# qo-100-pa-tec-controller.net
KiCad netlist of a schematic drawn in EAGLE
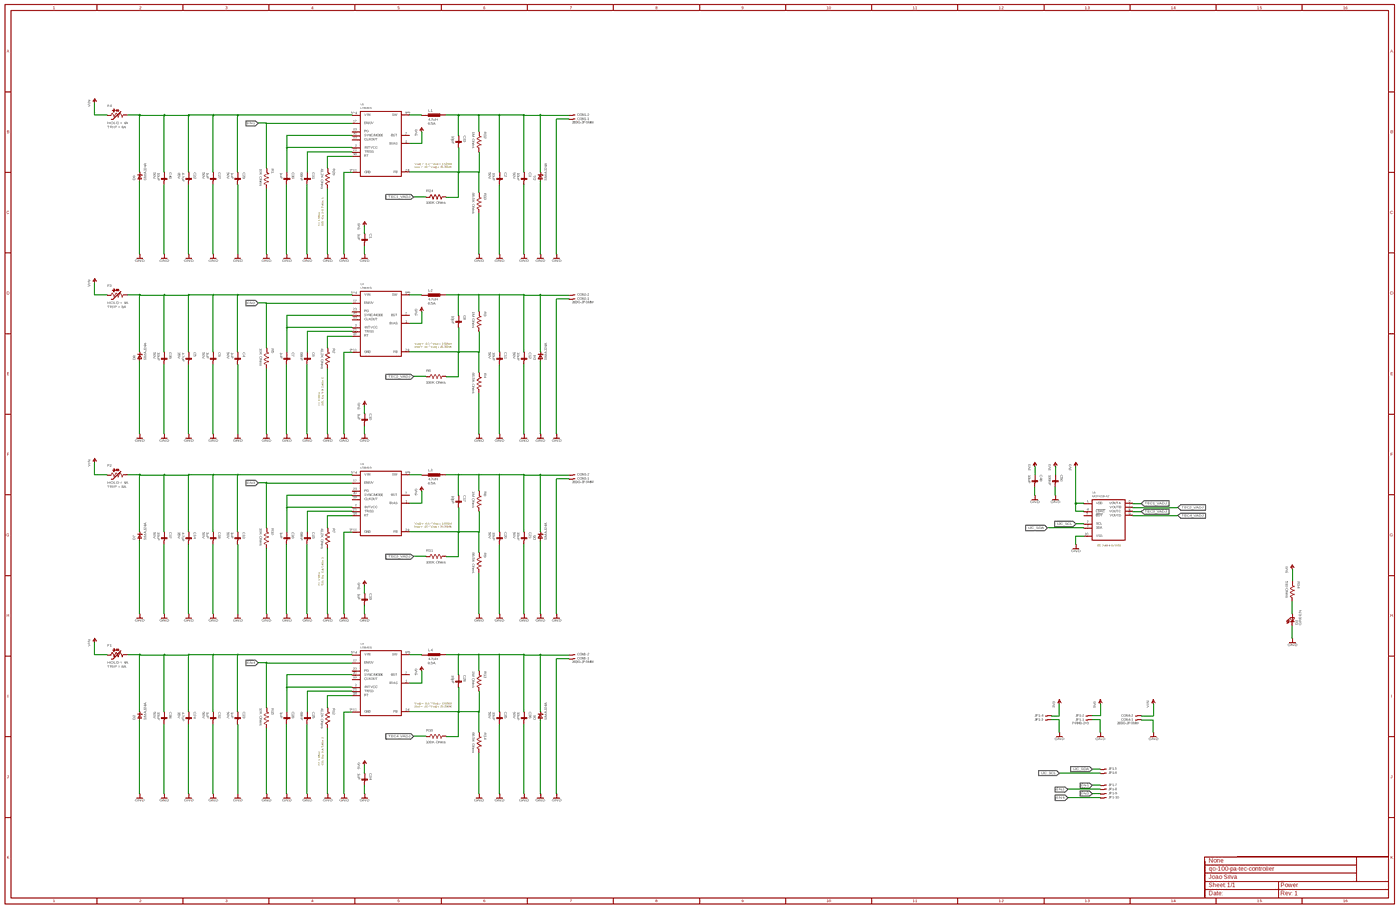
[diagram p0: schematic, sheet 1, overview]
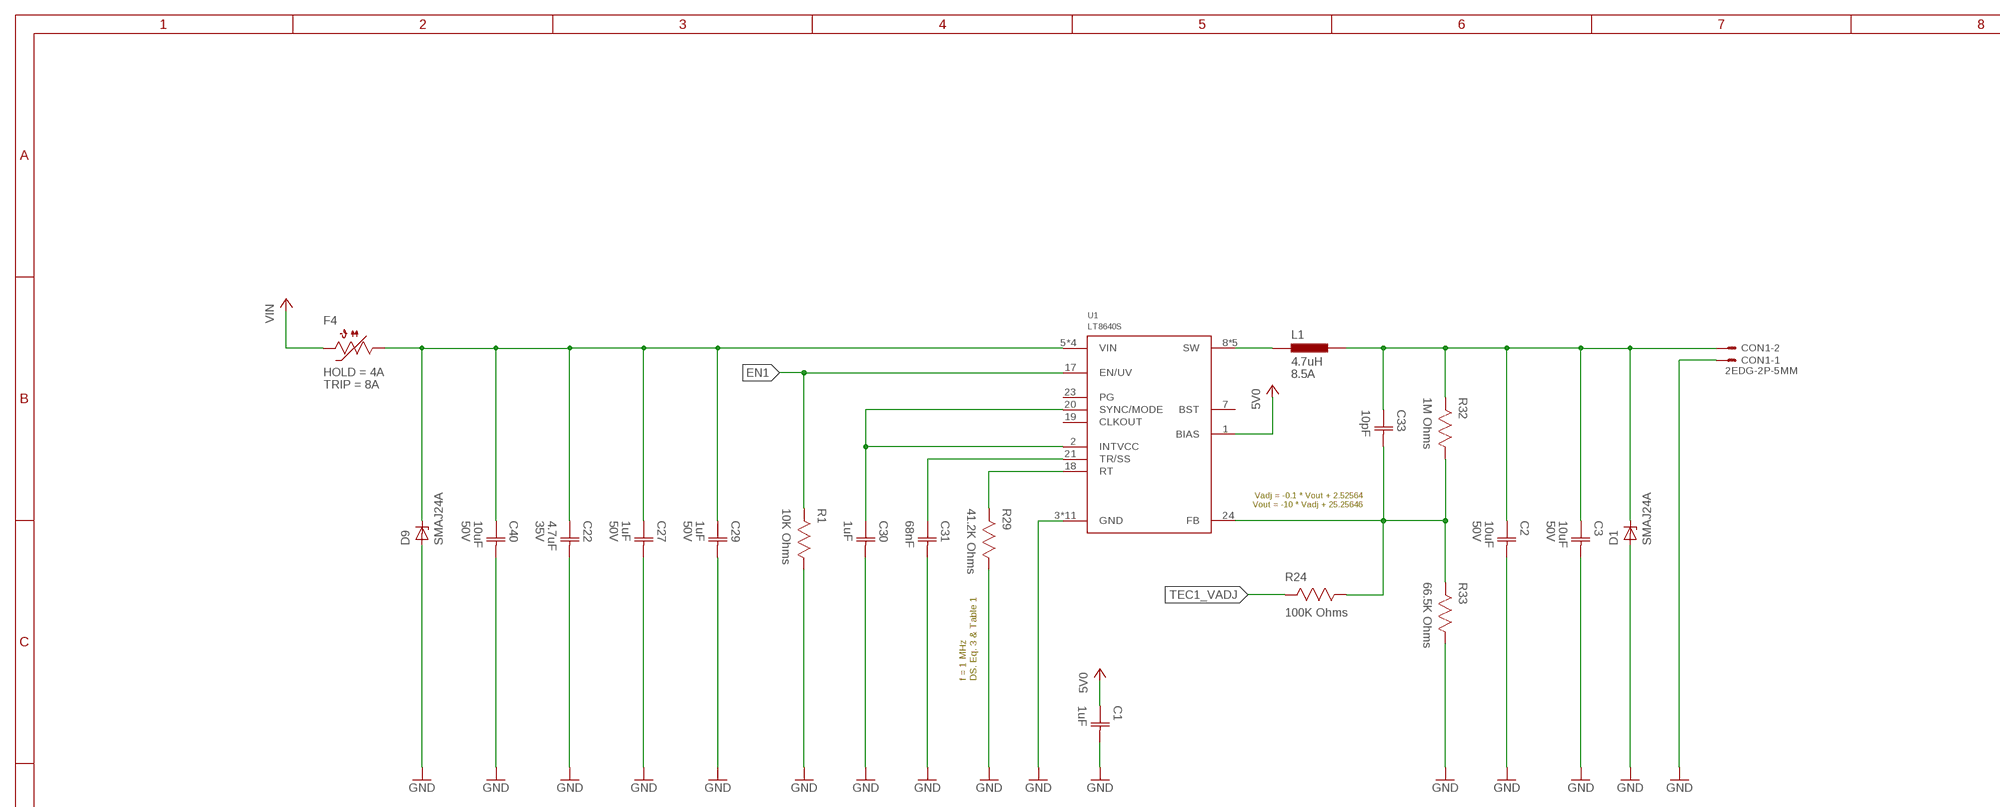
[diagram p1: schematic, sheet 1, part 1 of 4]
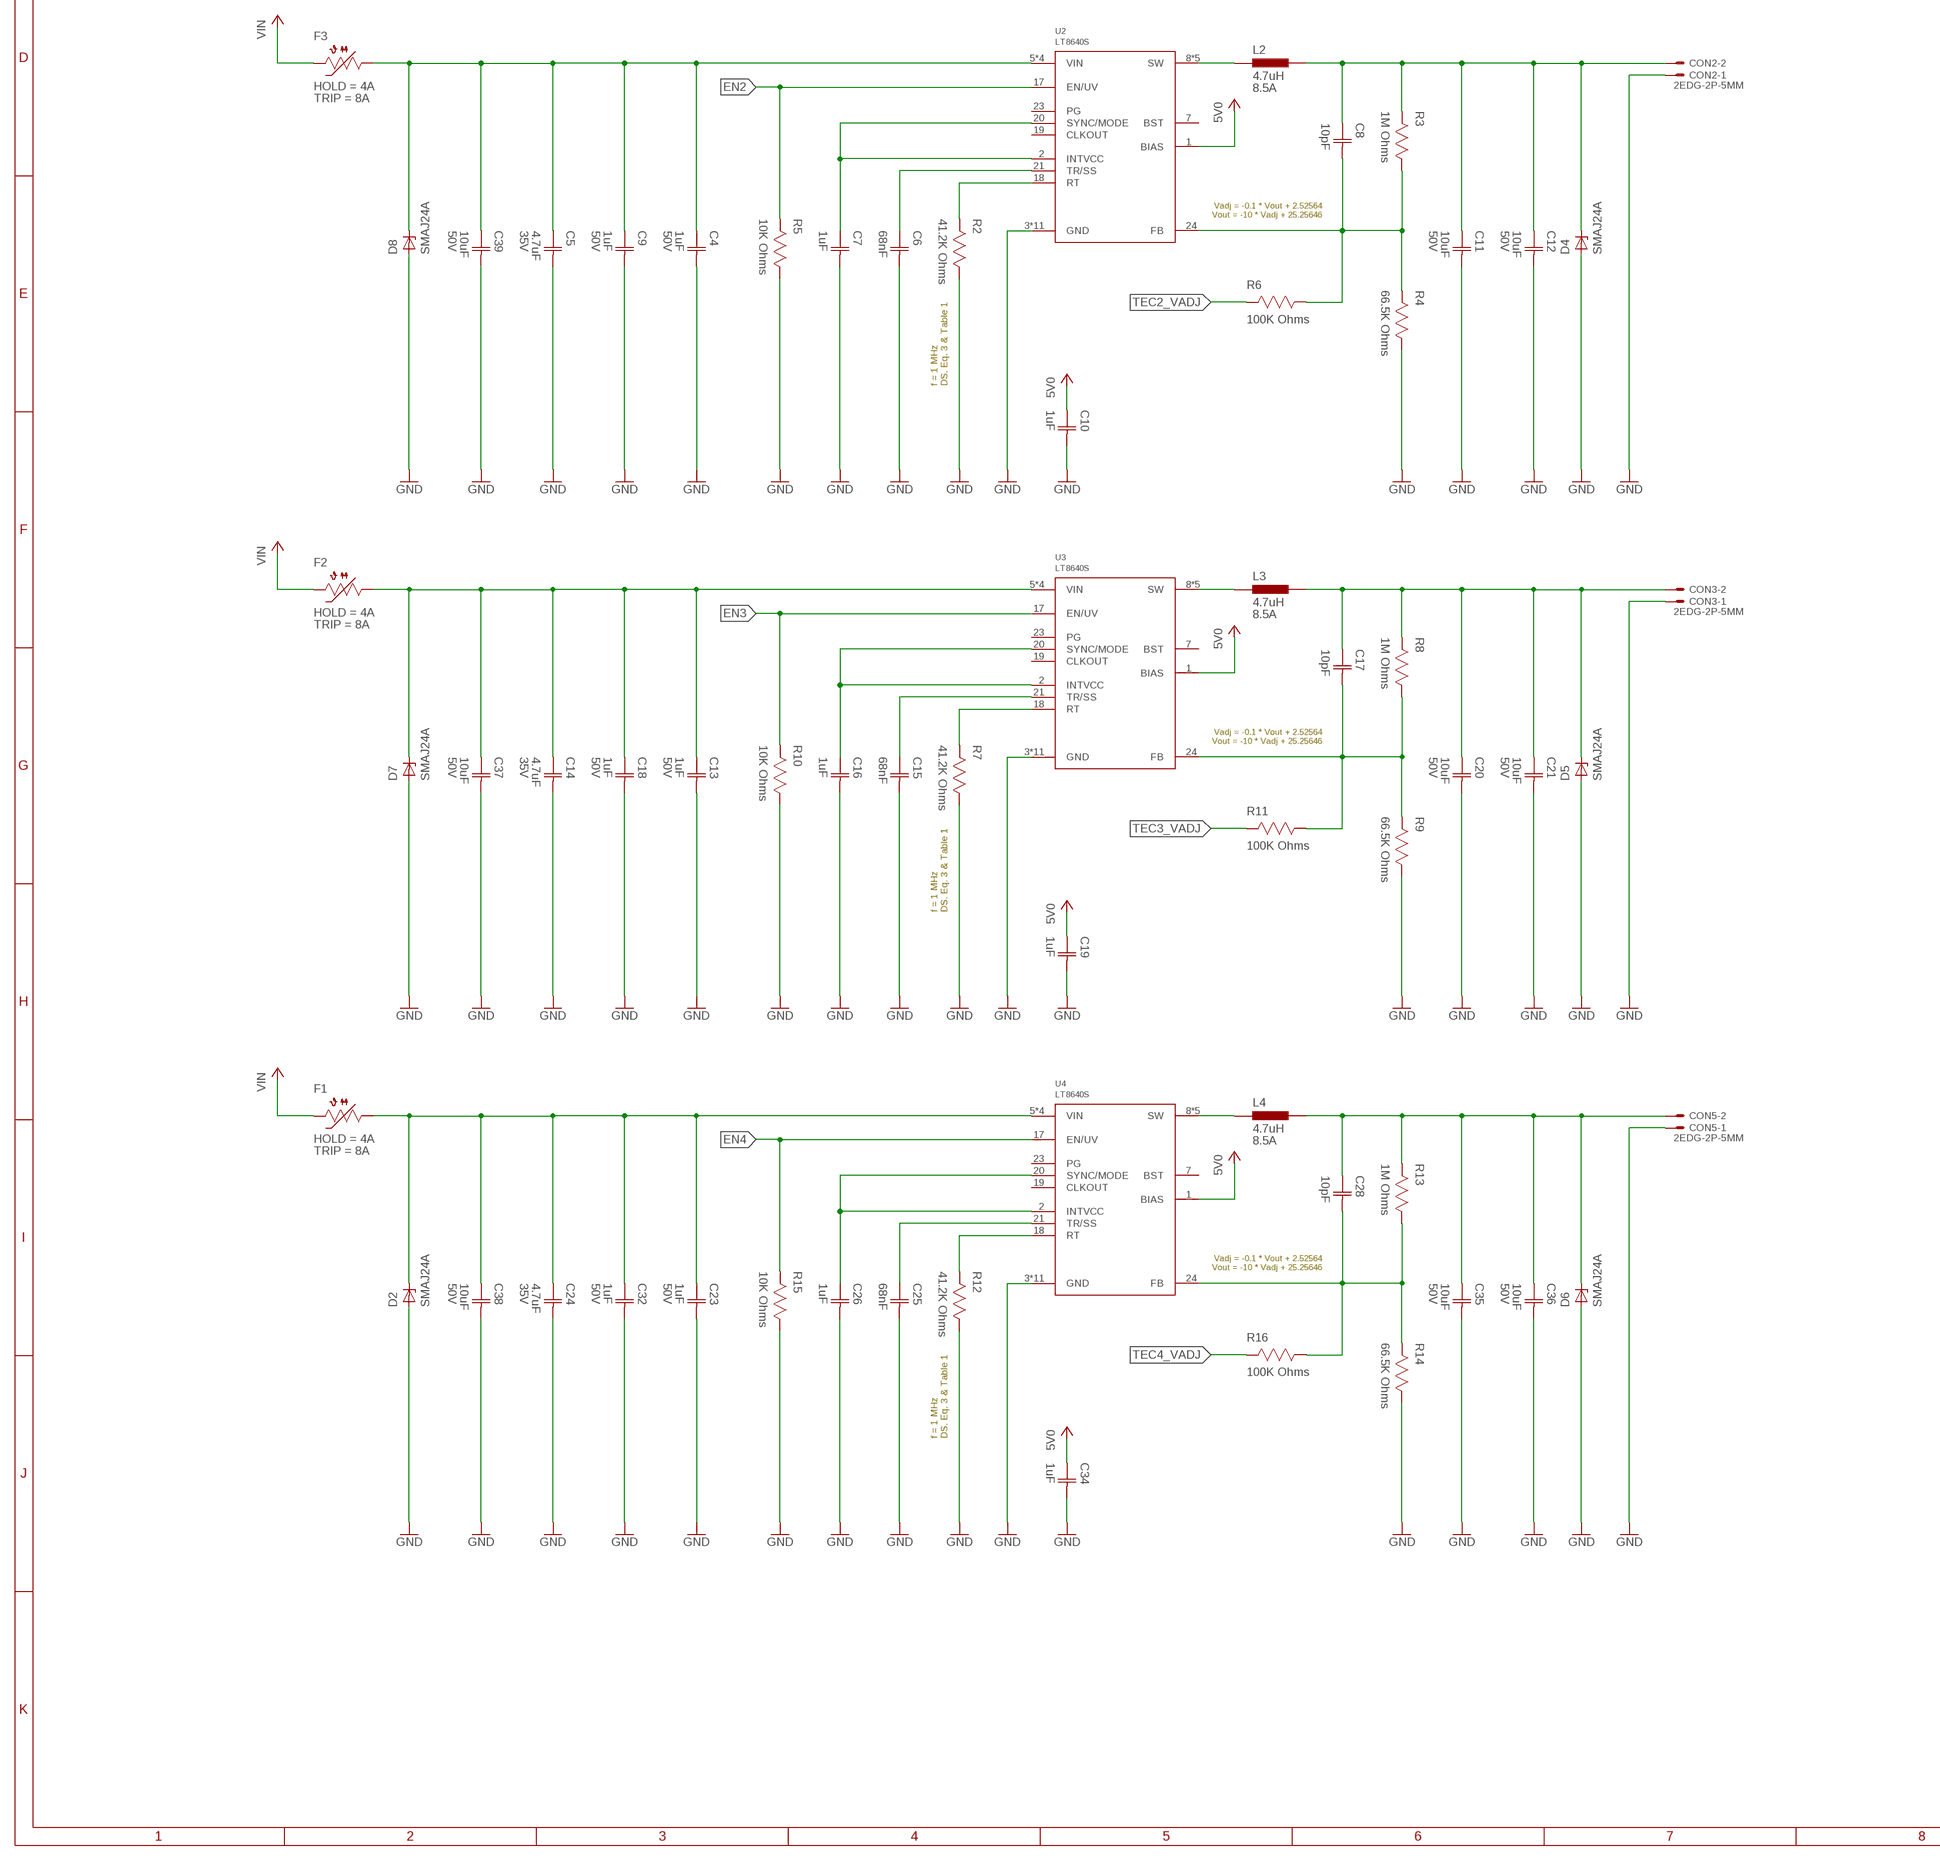
[diagram p2: schematic, sheet 1, part 2 of 4]
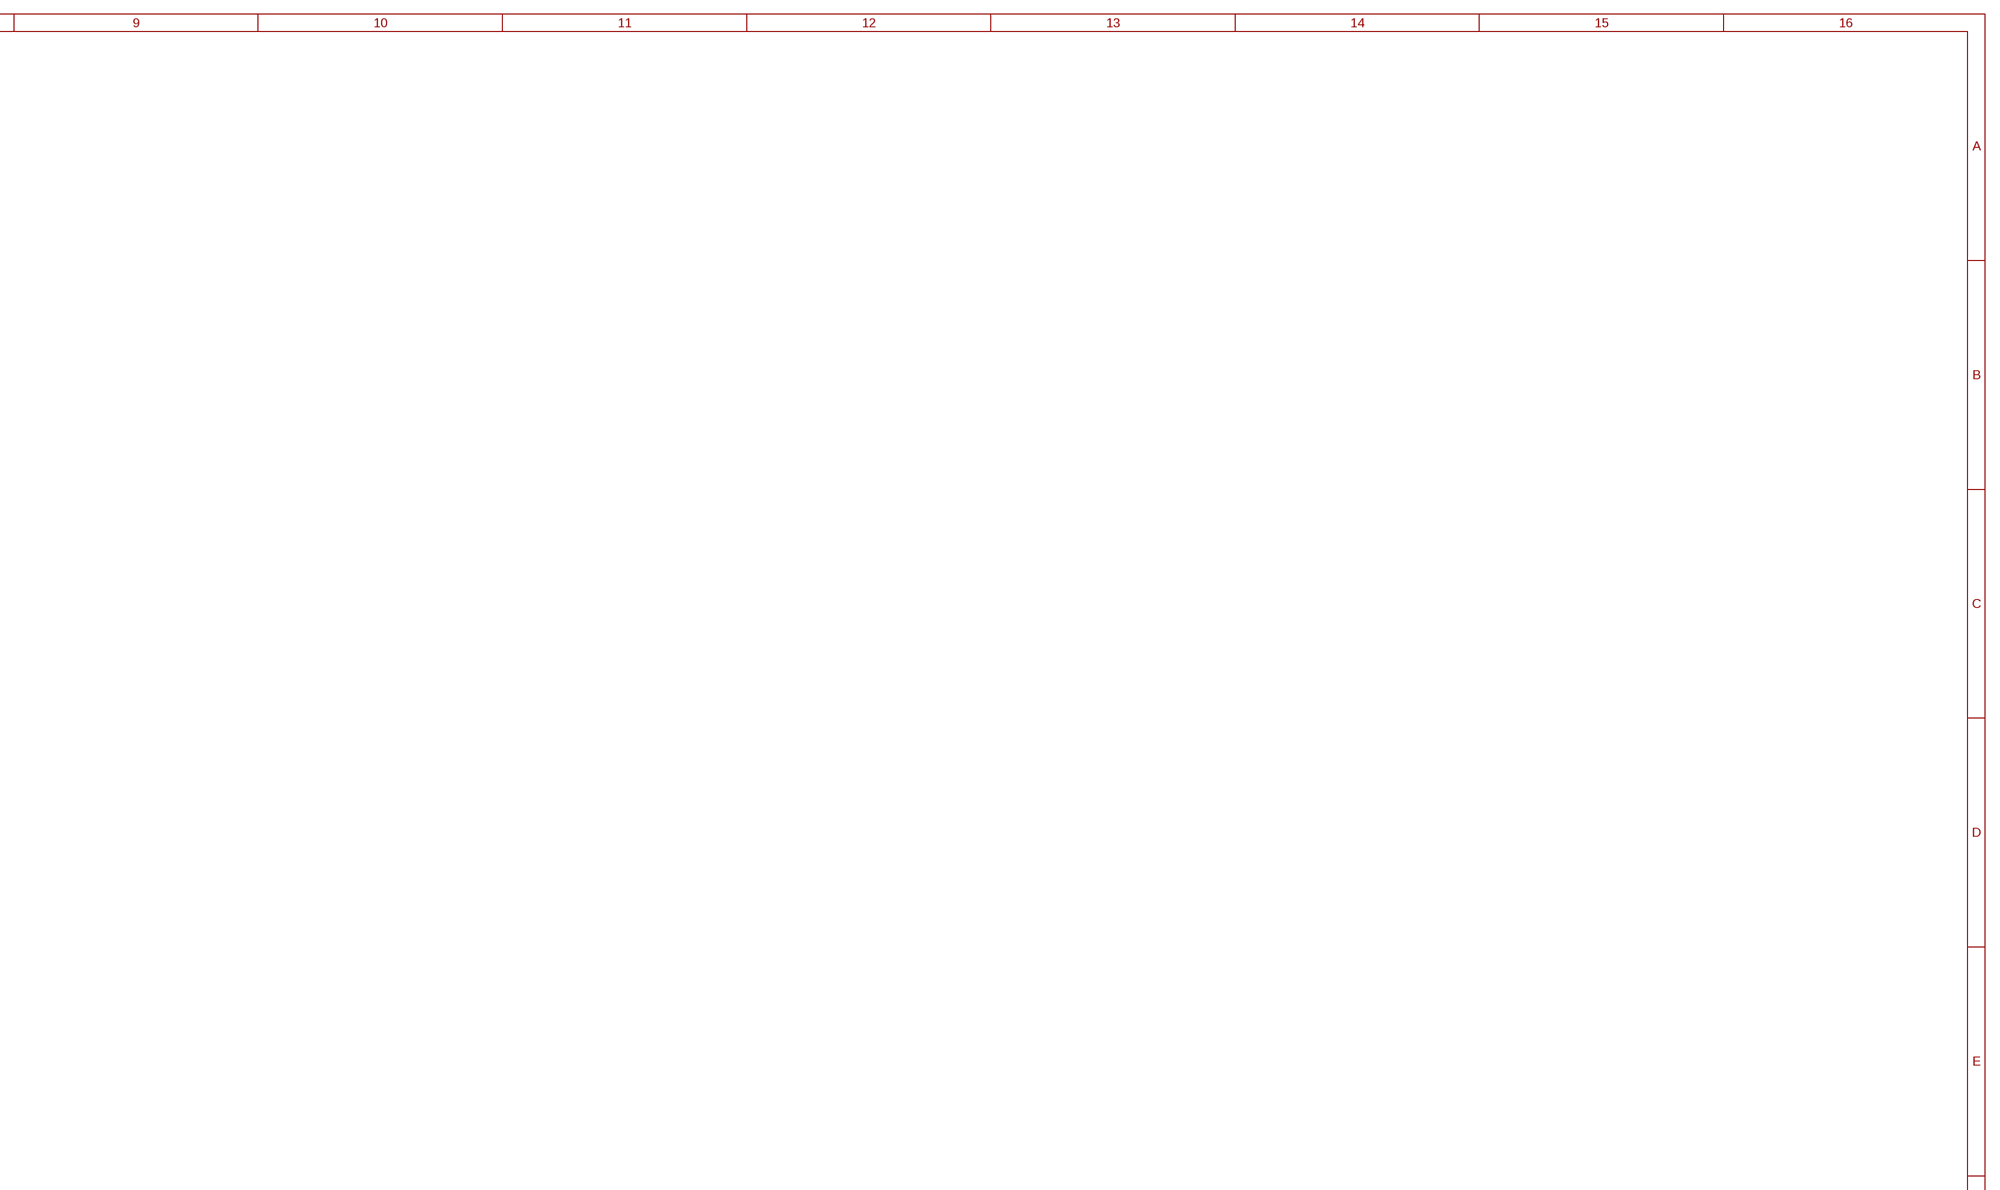
[diagram p3: schematic, sheet 1, part 3 of 4]
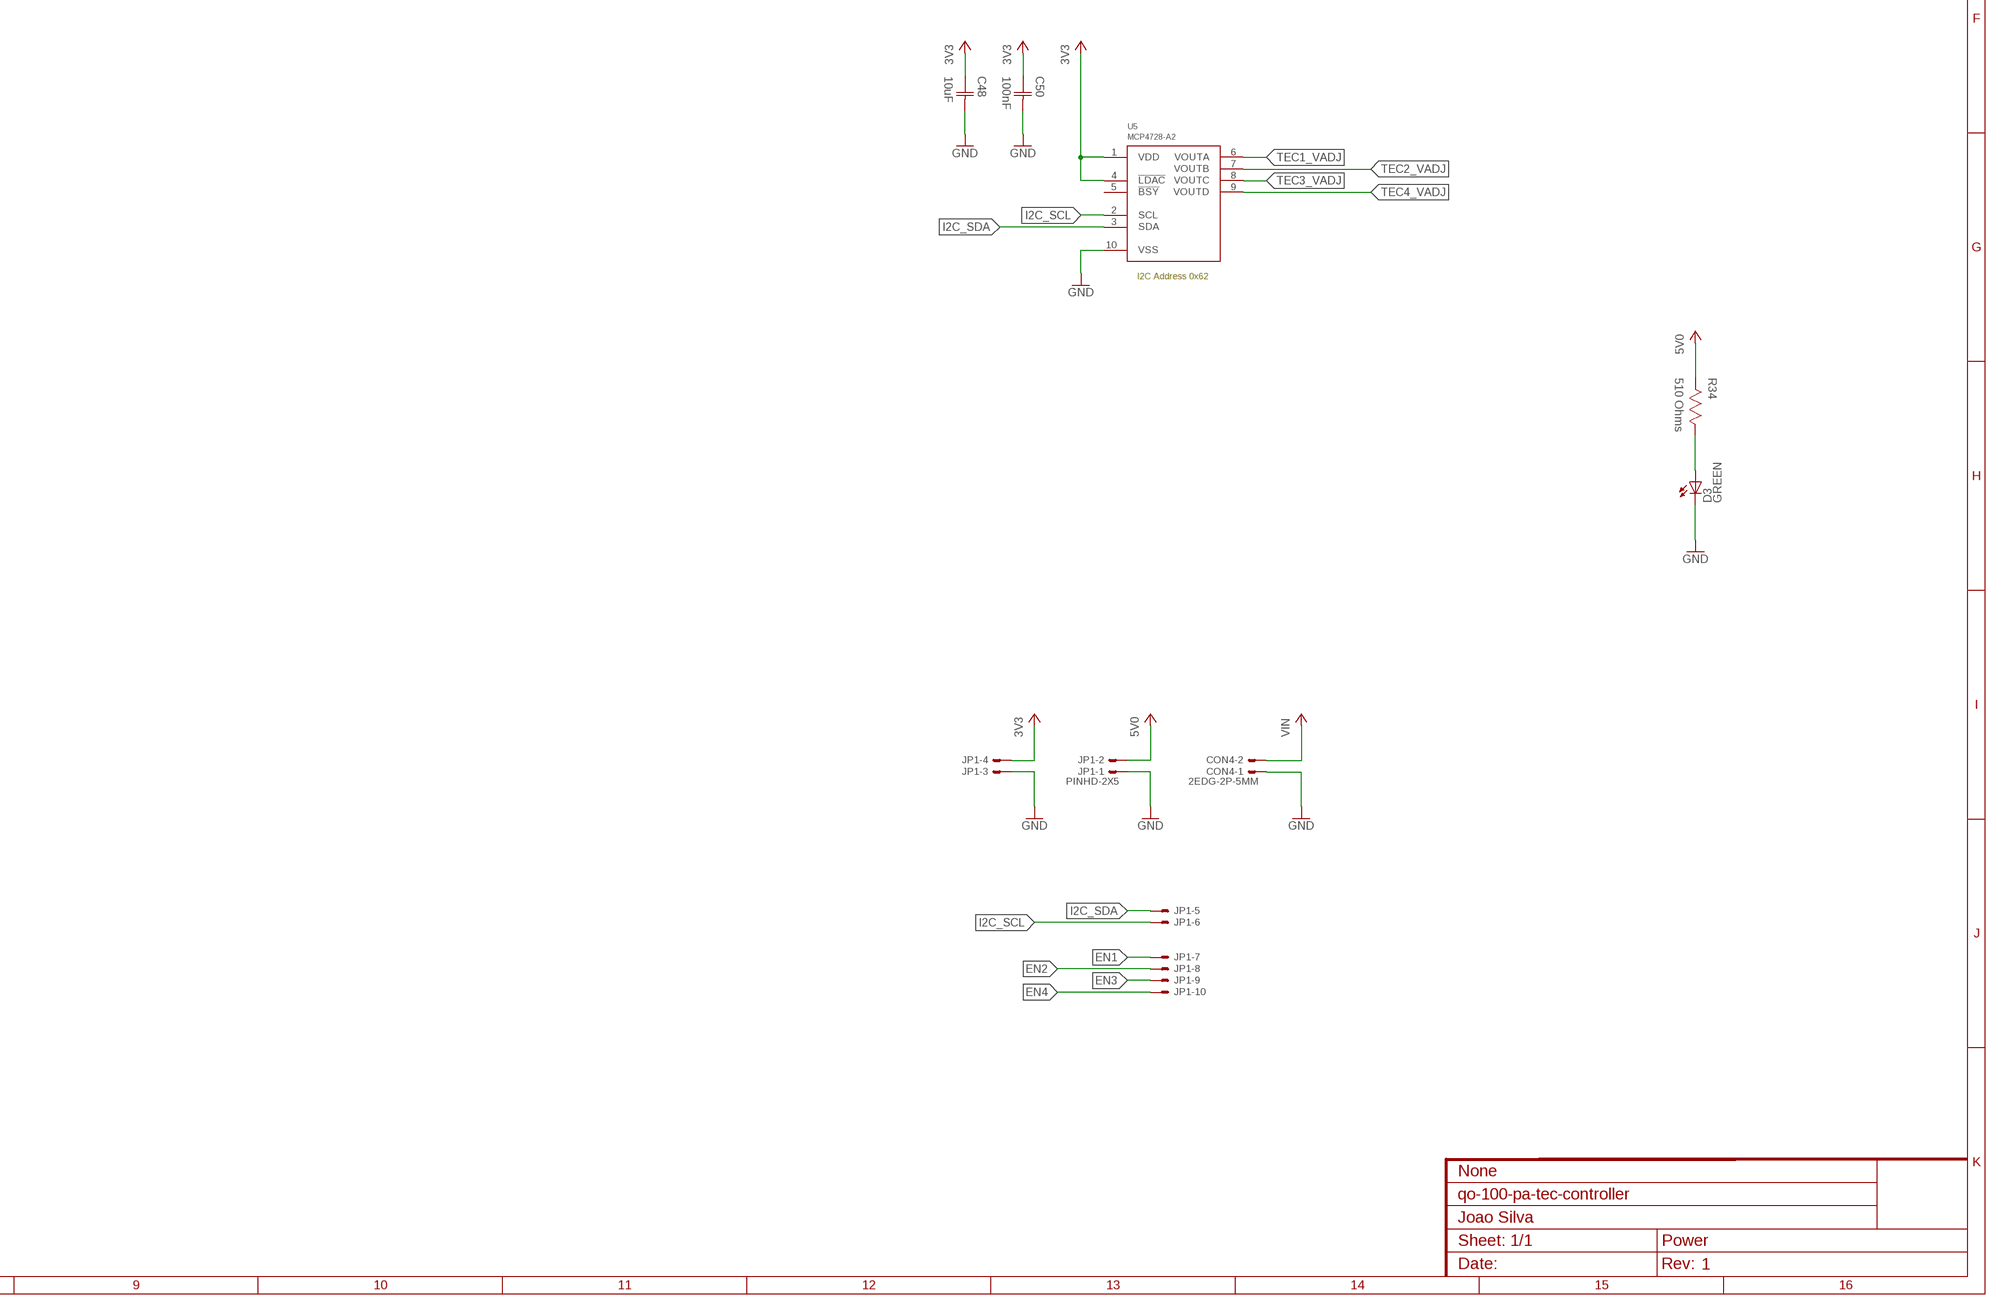
[diagram p4: schematic, sheet 1, part 4 of 4]

(export (version "E")
  (design (tool "Eeschema 10.0.6"))
  (components
    (comp (ref "C1")
      (value "1uF")
      (footprint "eagle-import:CAP0603")
      (libsource (lib "eagle-import") (part "CAPACITOR-0603"))
    )
    (comp (ref "C2")
      (value "10uF")
      (footprint "eagle-import:CAP1206")
      (fields (field (name "VOLTAGE") "50V"))
      (libsource (lib "eagle-import") (part "CAPACITOR-1206"))
    )
    (comp (ref "C3")
      (value "10uF")
      (footprint "eagle-import:CAP1206")
      (fields (field (name "VOLTAGE") "50V"))
      (libsource (lib "eagle-import") (part "CAPACITOR-1206"))
    )
    (comp (ref "C4")
      (value "1uF")
      (footprint "eagle-import:CAP0603")
      (fields (field (name "VOLTAGE") "50V"))
      (libsource (lib "eagle-import") (part "CAPACITOR-0603"))
    )
    (comp (ref "C5")
      (value "4.7uF")
      (footprint "eagle-import:CAP0603")
      (fields (field (name "VOLTAGE") "35V"))
      (libsource (lib "eagle-import") (part "CAPACITOR-0603"))
    )
    (comp (ref "C6")
      (value "68nF")
      (footprint "eagle-import:CAP0603")
      (libsource (lib "eagle-import") (part "CAPACITOR-0603"))
    )
    (comp (ref "C7")
      (value "1uF")
      (footprint "eagle-import:CAP0603")
      (libsource (lib "eagle-import") (part "CAPACITOR-0603"))
    )
    (comp (ref "C8")
      (value "10pF")
      (footprint "eagle-import:CAP0603")
      (libsource (lib "eagle-import") (part "CAPACITOR-0603"))
    )
    (comp (ref "C9")
      (value "1uF")
      (footprint "eagle-import:CAP0603")
      (fields (field (name "VOLTAGE") "50V"))
      (libsource (lib "eagle-import") (part "CAPACITOR-0603"))
    )
    (comp (ref "C10")
      (value "1uF")
      (footprint "eagle-import:CAP0603")
      (libsource (lib "eagle-import") (part "CAPACITOR-0603"))
    )
    (comp (ref "C11")
      (value "10uF")
      (footprint "eagle-import:CAP1206")
      (fields (field (name "VOLTAGE") "50V"))
      (libsource (lib "eagle-import") (part "CAPACITOR-1206"))
    )
    (comp (ref "C12")
      (value "10uF")
      (footprint "eagle-import:CAP1206")
      (fields (field (name "VOLTAGE") "50V"))
      (libsource (lib "eagle-import") (part "CAPACITOR-1206"))
    )
    (comp (ref "C13")
      (value "1uF")
      (footprint "eagle-import:CAP0603")
      (fields (field (name "VOLTAGE") "50V"))
      (libsource (lib "eagle-import") (part "CAPACITOR-0603"))
    )
    (comp (ref "C14")
      (value "4.7uF")
      (footprint "eagle-import:CAP0603")
      (fields (field (name "VOLTAGE") "35V"))
      (libsource (lib "eagle-import") (part "CAPACITOR-0603"))
    )
    (comp (ref "C15")
      (value "68nF")
      (footprint "eagle-import:CAP0603")
      (libsource (lib "eagle-import") (part "CAPACITOR-0603"))
    )
    (comp (ref "C16")
      (value "1uF")
      (footprint "eagle-import:CAP0603")
      (libsource (lib "eagle-import") (part "CAPACITOR-0603"))
    )
    (comp (ref "C17")
      (value "10pF")
      (footprint "eagle-import:CAP0603")
      (libsource (lib "eagle-import") (part "CAPACITOR-0603"))
    )
    (comp (ref "C18")
      (value "1uF")
      (footprint "eagle-import:CAP0603")
      (fields (field (name "VOLTAGE") "50V"))
      (libsource (lib "eagle-import") (part "CAPACITOR-0603"))
    )
    (comp (ref "C19")
      (value "1uF")
      (footprint "eagle-import:CAP0603")
      (libsource (lib "eagle-import") (part "CAPACITOR-0603"))
    )
    (comp (ref "C20")
      (value "10uF")
      (footprint "eagle-import:CAP1206")
      (fields (field (name "VOLTAGE") "50V"))
      (libsource (lib "eagle-import") (part "CAPACITOR-1206"))
    )
    (comp (ref "C21")
      (value "10uF")
      (footprint "eagle-import:CAP1206")
      (fields (field (name "VOLTAGE") "50V"))
      (libsource (lib "eagle-import") (part "CAPACITOR-1206"))
    )
    (comp (ref "C22")
      (value "4.7uF")
      (footprint "eagle-import:CAP0603")
      (fields (field (name "VOLTAGE") "35V"))
      (libsource (lib "eagle-import") (part "CAPACITOR-0603"))
    )
    (comp (ref "C23")
      (value "1uF")
      (footprint "eagle-import:CAP0603")
      (fields (field (name "VOLTAGE") "50V"))
      (libsource (lib "eagle-import") (part "CAPACITOR-0603"))
    )
    (comp (ref "C24")
      (value "4.7uF")
      (footprint "eagle-import:CAP0603")
      (fields (field (name "VOLTAGE") "35V"))
      (libsource (lib "eagle-import") (part "CAPACITOR-0603"))
    )
    (comp (ref "C25")
      (value "68nF")
      (footprint "eagle-import:CAP0603")
      (libsource (lib "eagle-import") (part "CAPACITOR-0603"))
    )
    (comp (ref "C26")
      (value "1uF")
      (footprint "eagle-import:CAP0603")
      (libsource (lib "eagle-import") (part "CAPACITOR-0603"))
    )
    (comp (ref "C27")
      (value "1uF")
      (footprint "eagle-import:CAP0603")
      (fields (field (name "VOLTAGE") "50V"))
      (libsource (lib "eagle-import") (part "CAPACITOR-0603"))
    )
    (comp (ref "C28")
      (value "10pF")
      (footprint "eagle-import:CAP0603")
      (libsource (lib "eagle-import") (part "CAPACITOR-0603"))
    )
    (comp (ref "C29")
      (value "1uF")
      (footprint "eagle-import:CAP0603")
      (fields (field (name "VOLTAGE") "50V"))
      (libsource (lib "eagle-import") (part "CAPACITOR-0603"))
    )
    (comp (ref "C30")
      (value "1uF")
      (footprint "eagle-import:CAP0603")
      (libsource (lib "eagle-import") (part "CAPACITOR-0603"))
    )
    (comp (ref "C31")
      (value "68nF")
      (footprint "eagle-import:CAP0603")
      (libsource (lib "eagle-import") (part "CAPACITOR-0603"))
    )
    (comp (ref "C32")
      (value "1uF")
      (footprint "eagle-import:CAP0603")
      (fields (field (name "VOLTAGE") "50V"))
      (libsource (lib "eagle-import") (part "CAPACITOR-0603"))
    )
    (comp (ref "C33")
      (value "10pF")
      (footprint "eagle-import:CAP0603")
      (libsource (lib "eagle-import") (part "CAPACITOR-0603"))
    )
    (comp (ref "C34")
      (value "1uF")
      (footprint "eagle-import:CAP0603")
      (libsource (lib "eagle-import") (part "CAPACITOR-0603"))
    )
    (comp (ref "C35")
      (value "10uF")
      (footprint "eagle-import:CAP1206")
      (fields (field (name "VOLTAGE") "50V"))
      (libsource (lib "eagle-import") (part "CAPACITOR-1206"))
    )
    (comp (ref "C36")
      (value "10uF")
      (footprint "eagle-import:CAP1206")
      (fields (field (name "VOLTAGE") "50V"))
      (libsource (lib "eagle-import") (part "CAPACITOR-1206"))
    )
    (comp (ref "C37")
      (value "10uF")
      (footprint "eagle-import:CAP1206")
      (fields (field (name "VOLTAGE") "50V"))
      (libsource (lib "eagle-import") (part "CAPACITOR-1206"))
    )
    (comp (ref "C38")
      (value "10uF")
      (footprint "eagle-import:CAP1206")
      (fields (field (name "VOLTAGE") "50V"))
      (libsource (lib "eagle-import") (part "CAPACITOR-1206"))
    )
    (comp (ref "C39")
      (value "10uF")
      (footprint "eagle-import:CAP1206")
      (fields (field (name "VOLTAGE") "50V"))
      (libsource (lib "eagle-import") (part "CAPACITOR-1206"))
    )
    (comp (ref "C40")
      (value "10uF")
      (footprint "eagle-import:CAP1206")
      (fields (field (name "VOLTAGE") "50V"))
      (libsource (lib "eagle-import") (part "CAPACITOR-1206"))
    )
    (comp (ref "C48")
      (value "10uF")
      (footprint "eagle-import:CAP0603")
      (libsource (lib "eagle-import") (part "CAPACITOR-0603"))
    )
    (comp (ref "C50")
      (value "100nF")
      (footprint "eagle-import:CAP0603")
      (libsource (lib "eagle-import") (part "CAPACITOR-0603"))
    )
    (comp (ref "CON1")
      (value "2EDG-2P-5MM")
      (footprint "eagle-import:2EDG-2P-5MM")
      (libsource (lib "eagle-import") (part "2EDG-2P-5MM"))
    )
    (comp (ref "CON2")
      (value "2EDG-2P-5MM")
      (footprint "eagle-import:2EDG-2P-5MM")
      (libsource (lib "eagle-import") (part "2EDG-2P-5MM"))
    )
    (comp (ref "CON3")
      (value "2EDG-2P-5MM")
      (footprint "eagle-import:2EDG-2P-5MM")
      (libsource (lib "eagle-import") (part "2EDG-2P-5MM"))
    )
    (comp (ref "CON4")
      (value "2EDG-2P-5MM")
      (footprint "eagle-import:2EDG-2P-5MM")
      (libsource (lib "eagle-import") (part "2EDG-2P-5MM"))
    )
    (comp (ref "CON5")
      (value "2EDG-2P-5MM")
      (footprint "eagle-import:2EDG-2P-5MM")
      (libsource (lib "eagle-import") (part "2EDG-2P-5MM"))
    )
    (comp (ref "D1")
      (value "SMAJ24A")
      (footprint "eagle-import:DO214AC")
      (fields (field (name "MF") "Littelfuse"))
      (libsource (lib "eagle-import") (part "SMAJA24"))
    )
    (comp (ref "D2")
      (value "SMAJ24A")
      (footprint "eagle-import:DO214AC")
      (fields (field (name "MF") "Littelfuse"))
      (libsource (lib "eagle-import") (part "SMAJA24"))
    )
    (comp (ref "D3")
      (value "LED0603")
      (footprint "eagle-import:0603")
      (fields (field (name "COLOR") "GREEN"))
      (libsource (lib "eagle-import") (part "LED0603"))
    )
    (comp (ref "D4")
      (value "SMAJ24A")
      (footprint "eagle-import:DO214AC")
      (fields (field (name "MF") "Littelfuse"))
      (libsource (lib "eagle-import") (part "SMAJA24"))
    )
    (comp (ref "D5")
      (value "SMAJ24A")
      (footprint "eagle-import:DO214AC")
      (fields (field (name "MF") "Littelfuse"))
      (libsource (lib "eagle-import") (part "SMAJA24"))
    )
    (comp (ref "D6")
      (value "SMAJ24A")
      (footprint "eagle-import:DO214AC")
      (fields (field (name "MF") "Littelfuse"))
      (libsource (lib "eagle-import") (part "SMAJA24"))
    )
    (comp (ref "D7")
      (value "SMAJ24A")
      (footprint "eagle-import:DO214AC")
      (fields (field (name "MF") "Littelfuse"))
      (libsource (lib "eagle-import") (part "SMAJA24"))
    )
    (comp (ref "D8")
      (value "SMAJ24A")
      (footprint "eagle-import:DO214AC")
      (fields (field (name "MF") "Littelfuse"))
      (libsource (lib "eagle-import") (part "SMAJA24"))
    )
    (comp (ref "D9")
      (value "SMAJ24A")
      (footprint "eagle-import:DO214AC")
      (fields (field (name "MF") "Littelfuse"))
      (libsource (lib "eagle-import") (part "SMAJA24"))
    )
    (comp (ref "F1")
      (value "2.6A Hold")
      (footprint "eagle-import:1206")
      (fields (field (name "HOLD") "4A") (field (name "TRIP") "8A"))
      (libsource (lib "eagle-import") (part "PTC1206"))
    )
    (comp (ref "F2")
      (value "2.6A Hold")
      (footprint "eagle-import:1206")
      (fields (field (name "HOLD") "4A") (field (name "TRIP") "8A"))
      (libsource (lib "eagle-import") (part "PTC1206"))
    )
    (comp (ref "F3")
      (value "2.6A Hold")
      (footprint "eagle-import:1206")
      (fields (field (name "HOLD") "4A") (field (name "TRIP") "8A"))
      (libsource (lib "eagle-import") (part "PTC1206"))
    )
    (comp (ref "F4")
      (value "2.6A Hold")
      (footprint "eagle-import:1206")
      (fields (field (name "HOLD") "4A") (field (name "TRIP") "8A"))
      (libsource (lib "eagle-import") (part "PTC1206"))
    )
    (comp (ref "JP1")
      (value "PINHD-2X5")
      (footprint "eagle-import:2X05")
      (libsource (lib "eagle-import") (part "PINHD-2X5"))
    )
    (comp (ref "L1")
      (value "4.7uH")
      (footprint "eagle-import:IND1040")
      (fields (field (name "CURRENT") "8.5A"))
      (libsource (lib "eagle-import") (part "INDUCTOR-10.2X10.2X4MM"))
    )
    (comp (ref "L2")
      (value "4.7uH")
      (footprint "eagle-import:IND1040")
      (fields (field (name "CURRENT") "8.5A"))
      (libsource (lib "eagle-import") (part "INDUCTOR-10.2X10.2X4MM"))
    )
    (comp (ref "L3")
      (value "4.7uH")
      (footprint "eagle-import:IND1040")
      (fields (field (name "CURRENT") "8.5A"))
      (libsource (lib "eagle-import") (part "INDUCTOR-10.2X10.2X4MM"))
    )
    (comp (ref "L4")
      (value "4.7uH")
      (footprint "eagle-import:IND1040")
      (fields (field (name "CURRENT") "8.5A"))
      (libsource (lib "eagle-import") (part "INDUCTOR-10.2X10.2X4MM"))
    )
    (comp (ref "R1")
      (value "10K Ohms")
      (footprint "eagle-import:RES0603")
      (libsource (lib "eagle-import") (part "RESISTOR-0603"))
    )
    (comp (ref "R2")
      (value "41.2K Ohms")
      (footprint "eagle-import:RES0603")
      (libsource (lib "eagle-import") (part "RESISTOR-0603"))
    )
    (comp (ref "R3")
      (value "1M Ohms")
      (footprint "eagle-import:RES0603")
      (libsource (lib "eagle-import") (part "RESISTOR-0603"))
    )
    (comp (ref "R4")
      (value "66.5K Ohms")
      (footprint "eagle-import:RES0603")
      (libsource (lib "eagle-import") (part "RESISTOR-0603"))
    )
    (comp (ref "R5")
      (value "10K Ohms")
      (footprint "eagle-import:RES0603")
      (libsource (lib "eagle-import") (part "RESISTOR-0603"))
    )
    (comp (ref "R6")
      (value "100K Ohms")
      (footprint "eagle-import:RES0603")
      (libsource (lib "eagle-import") (part "RESISTOR-0603"))
    )
    (comp (ref "R7")
      (value "41.2K Ohms")
      (footprint "eagle-import:RES0603")
      (libsource (lib "eagle-import") (part "RESISTOR-0603"))
    )
    (comp (ref "R8")
      (value "1M Ohms")
      (footprint "eagle-import:RES0603")
      (libsource (lib "eagle-import") (part "RESISTOR-0603"))
    )
    (comp (ref "R9")
      (value "66.5K Ohms")
      (footprint "eagle-import:RES0603")
      (libsource (lib "eagle-import") (part "RESISTOR-0603"))
    )
    (comp (ref "R10")
      (value "10K Ohms")
      (footprint "eagle-import:RES0603")
      (libsource (lib "eagle-import") (part "RESISTOR-0603"))
    )
    (comp (ref "R11")
      (value "100K Ohms")
      (footprint "eagle-import:RES0603")
      (libsource (lib "eagle-import") (part "RESISTOR-0603"))
    )
    (comp (ref "R12")
      (value "41.2K Ohms")
      (footprint "eagle-import:RES0603")
      (libsource (lib "eagle-import") (part "RESISTOR-0603"))
    )
    (comp (ref "R13")
      (value "1M Ohms")
      (footprint "eagle-import:RES0603")
      (libsource (lib "eagle-import") (part "RESISTOR-0603"))
    )
    (comp (ref "R14")
      (value "66.5K Ohms")
      (footprint "eagle-import:RES0603")
      (libsource (lib "eagle-import") (part "RESISTOR-0603"))
    )
    (comp (ref "R15")
      (value "10K Ohms")
      (footprint "eagle-import:RES0603")
      (libsource (lib "eagle-import") (part "RESISTOR-0603"))
    )
    (comp (ref "R16")
      (value "100K Ohms")
      (footprint "eagle-import:RES0603")
      (libsource (lib "eagle-import") (part "RESISTOR-0603"))
    )
    (comp (ref "R24")
      (value "100K Ohms")
      (footprint "eagle-import:RES0603")
      (libsource (lib "eagle-import") (part "RESISTOR-0603"))
    )
    (comp (ref "R29")
      (value "41.2K Ohms")
      (footprint "eagle-import:RES0603")
      (libsource (lib "eagle-import") (part "RESISTOR-0603"))
    )
    (comp (ref "R32")
      (value "1M Ohms")
      (footprint "eagle-import:RES0603")
      (libsource (lib "eagle-import") (part "RESISTOR-0603"))
    )
    (comp (ref "R33")
      (value "66.5K Ohms")
      (footprint "eagle-import:RES0603")
      (libsource (lib "eagle-import") (part "RESISTOR-0603"))
    )
    (comp (ref "R34")
      (value "510 Ohms")
      (footprint "eagle-import:RES0603")
      (libsource (lib "eagle-import") (part "RESISTOR-0603"))
    )
    (comp (ref "U1")
      (value "LT8640S")
      (footprint "eagle-import:QFN24_CORNER")
      (libsource (lib "eagle-import") (part "LT8640S"))
    )
    (comp (ref "U2")
      (value "LT8640S")
      (footprint "eagle-import:QFN24_CORNER")
      (libsource (lib "eagle-import") (part "LT8640S"))
    )
    (comp (ref "U3")
      (value "LT8640S")
      (footprint "eagle-import:QFN24_CORNER")
      (libsource (lib "eagle-import") (part "LT8640S"))
    )
    (comp (ref "U4")
      (value "LT8640S")
      (footprint "eagle-import:QFN24_CORNER")
      (libsource (lib "eagle-import") (part "LT8640S"))
    )
    (comp (ref "U5")
      (value "MCP4728-A2")
      (footprint "eagle-import:MSOP10")
      (libsource (lib "eagle-import") (part "MCP4728-A2"))
    )
  )
  (nets
    (net (code "1") (name "3V3") (class "Default")
      (node (ref "C48") (pin "1") (pinfunction "C1_1") (pintype "passive"))
      (node (ref "C50") (pin "1") (pinfunction "C1_1") (pintype "passive"))
      (node (ref "JP1") (pin "4") (pinfunction "S_4") (pintype "passive"))
      (node (ref "U5") (pin "1") (pinfunction "VDD_1") (pintype "bidirectional"))
      (node (ref "U5") (pin "4") (pinfunction "~{LDAC}_4") (pintype "bidirectional"))
    )
    (net (code "2") (name "5V0") (class "Default")
      (node (ref "C1") (pin "1") (pinfunction "C1_1") (pintype "passive"))
      (node (ref "C10") (pin "1") (pinfunction "C1_1") (pintype "passive"))
      (node (ref "C19") (pin "1") (pinfunction "C1_1") (pintype "passive"))
      (node (ref "C34") (pin "1") (pinfunction "C1_1") (pintype "passive"))
      (node (ref "JP1") (pin "2") (pinfunction "S_2") (pintype "passive"))
      (node (ref "R34") (pin "2") (pinfunction "2_2") (pintype "passive"))
      (node (ref "U1") (pin "1") (pinfunction "BIAS_1") (pintype "bidirectional"))
      (node (ref "U2") (pin "1") (pinfunction "BIAS_1") (pintype "bidirectional"))
      (node (ref "U3") (pin "1") (pinfunction "BIAS_1") (pintype "bidirectional"))
      (node (ref "U4") (pin "1") (pinfunction "BIAS_1") (pintype "bidirectional"))
    )
    (net (code "3") (name "EN1") (class "Default")
      (node (ref "JP1") (pin "7") (pinfunction "S_7") (pintype "passive"))
      (node (ref "R1") (pin "2") (pinfunction "2_2") (pintype "passive"))
      (node (ref "U1") (pin "17") (pinfunction "EN/UV_17") (pintype "bidirectional"))
    )
    (net (code "4") (name "EN2") (class "Default")
      (node (ref "JP1") (pin "8") (pinfunction "S_8") (pintype "passive"))
      (node (ref "R5") (pin "2") (pinfunction "2_2") (pintype "passive"))
      (node (ref "U2") (pin "17") (pinfunction "EN/UV_17") (pintype "bidirectional"))
    )
    (net (code "5") (name "EN3") (class "Default")
      (node (ref "JP1") (pin "9") (pinfunction "S_9") (pintype "passive"))
      (node (ref "R10") (pin "2") (pinfunction "2_2") (pintype "passive"))
      (node (ref "U3") (pin "17") (pinfunction "EN/UV_17") (pintype "bidirectional"))
    )
    (net (code "6") (name "EN4") (class "Default")
      (node (ref "JP1") (pin "10") (pinfunction "S_10") (pintype "passive"))
      (node (ref "R15") (pin "2") (pinfunction "2_2") (pintype "passive"))
      (node (ref "U4") (pin "17") (pinfunction "EN/UV_17") (pintype "bidirectional"))
    )
    (net (code "7") (name "GND") (class "Default")
      (node (ref "C1") (pin "2") (pinfunction "C2_2") (pintype "passive"))
      (node (ref "C10") (pin "2") (pinfunction "C2_2") (pintype "passive"))
      (node (ref "C11") (pin "2") (pinfunction "C2_2") (pintype "passive"))
      (node (ref "C12") (pin "2") (pinfunction "C2_2") (pintype "passive"))
      (node (ref "C13") (pin "2") (pinfunction "C2_2") (pintype "passive"))
      (node (ref "C14") (pin "2") (pinfunction "C2_2") (pintype "passive"))
      (node (ref "C15") (pin "2") (pinfunction "C2_2") (pintype "passive"))
      (node (ref "C16") (pin "2") (pinfunction "C2_2") (pintype "passive"))
      (node (ref "C18") (pin "2") (pinfunction "C2_2") (pintype "passive"))
      (node (ref "C19") (pin "2") (pinfunction "C2_2") (pintype "passive"))
      (node (ref "C2") (pin "2") (pinfunction "C2_2") (pintype "passive"))
      (node (ref "C20") (pin "2") (pinfunction "C2_2") (pintype "passive"))
      (node (ref "C21") (pin "2") (pinfunction "C2_2") (pintype "passive"))
      (node (ref "C22") (pin "2") (pinfunction "C2_2") (pintype "passive"))
      (node (ref "C23") (pin "2") (pinfunction "C2_2") (pintype "passive"))
      (node (ref "C24") (pin "2") (pinfunction "C2_2") (pintype "passive"))
      (node (ref "C25") (pin "2") (pinfunction "C2_2") (pintype "passive"))
      (node (ref "C26") (pin "2") (pinfunction "C2_2") (pintype "passive"))
      (node (ref "C27") (pin "2") (pinfunction "C2_2") (pintype "passive"))
      (node (ref "C29") (pin "2") (pinfunction "C2_2") (pintype "passive"))
      (node (ref "C3") (pin "2") (pinfunction "C2_2") (pintype "passive"))
      (node (ref "C30") (pin "2") (pinfunction "C2_2") (pintype "passive"))
      (node (ref "C31") (pin "2") (pinfunction "C2_2") (pintype "passive"))
      (node (ref "C32") (pin "2") (pinfunction "C2_2") (pintype "passive"))
      (node (ref "C34") (pin "2") (pinfunction "C2_2") (pintype "passive"))
      (node (ref "C35") (pin "2") (pinfunction "C2_2") (pintype "passive"))
      (node (ref "C36") (pin "2") (pinfunction "C2_2") (pintype "passive"))
      (node (ref "C37") (pin "2") (pinfunction "C2_2") (pintype "passive"))
      (node (ref "C38") (pin "2") (pinfunction "C2_2") (pintype "passive"))
      (node (ref "C39") (pin "2") (pinfunction "C2_2") (pintype "passive"))
      (node (ref "C4") (pin "2") (pinfunction "C2_2") (pintype "passive"))
      (node (ref "C40") (pin "2") (pinfunction "C2_2") (pintype "passive"))
      (node (ref "C48") (pin "2") (pinfunction "C2_2") (pintype "passive"))
      (node (ref "C5") (pin "2") (pinfunction "C2_2") (pintype "passive"))
      (node (ref "C50") (pin "2") (pinfunction "C2_2") (pintype "passive"))
      (node (ref "C6") (pin "2") (pinfunction "C2_2") (pintype "passive"))
      (node (ref "C7") (pin "2") (pinfunction "C2_2") (pintype "passive"))
      (node (ref "C9") (pin "2") (pinfunction "C2_2") (pintype "passive"))
      (node (ref "CON1") (pin "P$1") (pinfunction "S_P$1") (pintype "passive"))
      (node (ref "CON2") (pin "P$1") (pinfunction "S_P$1") (pintype "passive"))
      (node (ref "CON3") (pin "P$1") (pinfunction "S_P$1") (pintype "passive"))
      (node (ref "CON4") (pin "P$1") (pinfunction "S_P$1") (pintype "passive"))
      (node (ref "CON5") (pin "P$1") (pinfunction "S_P$1") (pintype "passive"))
      (node (ref "D1") (pin "A") (pinfunction "A_A") (pintype "passive"))
      (node (ref "D2") (pin "A") (pinfunction "A_A") (pintype "passive"))
      (node (ref "D3") (pin "C") (pinfunction "C_C") (pintype "passive"))
      (node (ref "D4") (pin "A") (pinfunction "A_A") (pintype "passive"))
      (node (ref "D5") (pin "A") (pinfunction "A_A") (pintype "passive"))
      (node (ref "D6") (pin "A") (pinfunction "A_A") (pintype "passive"))
      (node (ref "D7") (pin "A") (pinfunction "A_A") (pintype "passive"))
      (node (ref "D8") (pin "A") (pinfunction "A_A") (pintype "passive"))
      (node (ref "D9") (pin "A") (pinfunction "A_A") (pintype "passive"))
      (node (ref "JP1") (pin "1") (pinfunction "S_1") (pintype "passive"))
      (node (ref "JP1") (pin "3") (pinfunction "S_3") (pintype "passive"))
      (node (ref "R1") (pin "1") (pinfunction "1_1") (pintype "passive"))
      (node (ref "R10") (pin "1") (pinfunction "1_1") (pintype "passive"))
      (node (ref "R12") (pin "1") (pinfunction "1_1") (pintype "passive"))
      (node (ref "R14") (pin "1") (pinfunction "1_1") (pintype "passive"))
      (node (ref "R15") (pin "1") (pinfunction "1_1") (pintype "passive"))
      (node (ref "R2") (pin "1") (pinfunction "1_1") (pintype "passive"))
      (node (ref "R29") (pin "1") (pinfunction "1_1") (pintype "passive"))
      (node (ref "R33") (pin "1") (pinfunction "1_1") (pintype "passive"))
      (node (ref "R4") (pin "1") (pinfunction "1_1") (pintype "passive"))
      (node (ref "R5") (pin "1") (pinfunction "1_1") (pintype "passive"))
      (node (ref "R7") (pin "1") (pinfunction "1_1") (pintype "passive"))
      (node (ref "R9") (pin "1") (pinfunction "1_1") (pintype "passive"))
      (node (ref "U1") (pin "16") (pinfunction "GND_16") (pintype "bidirectional"))
      (node (ref "U1") (pin "22") (pinfunction "GND_22") (pintype "bidirectional"))
      (node (ref "U1") (pin "25") (pinfunction "GND_25") (pintype "bidirectional"))
      (node (ref "U1") (pin "26") (pinfunction "GND_26") (pintype "bidirectional"))
      (node (ref "U1") (pin "27") (pinfunction "GND_27") (pintype "bidirectional"))
      (node (ref "U1") (pin "28") (pinfunction "GND_28") (pintype "bidirectional"))
      (node (ref "U1") (pin "29") (pinfunction "GND_29") (pintype "bidirectional"))
      (node (ref "U1") (pin "3") (pinfunction "GND_3") (pintype "bidirectional"))
      (node (ref "U1") (pin "30") (pinfunction "GND_30") (pintype "bidirectional"))
      (node (ref "U1") (pin "31") (pinfunction "GND_31") (pintype "bidirectional"))
      (node (ref "U1") (pin "32") (pinfunction "GND_32") (pintype "bidirectional"))
      (node (ref "U2") (pin "16") (pinfunction "GND_16") (pintype "bidirectional"))
      (node (ref "U2") (pin "22") (pinfunction "GND_22") (pintype "bidirectional"))
      (node (ref "U2") (pin "25") (pinfunction "GND_25") (pintype "bidirectional"))
      (node (ref "U2") (pin "26") (pinfunction "GND_26") (pintype "bidirectional"))
      (node (ref "U2") (pin "27") (pinfunction "GND_27") (pintype "bidirectional"))
      (node (ref "U2") (pin "28") (pinfunction "GND_28") (pintype "bidirectional"))
      (node (ref "U2") (pin "29") (pinfunction "GND_29") (pintype "bidirectional"))
      (node (ref "U2") (pin "3") (pinfunction "GND_3") (pintype "bidirectional"))
      (node (ref "U2") (pin "30") (pinfunction "GND_30") (pintype "bidirectional"))
      (node (ref "U2") (pin "31") (pinfunction "GND_31") (pintype "bidirectional"))
      (node (ref "U2") (pin "32") (pinfunction "GND_32") (pintype "bidirectional"))
      (node (ref "U3") (pin "16") (pinfunction "GND_16") (pintype "bidirectional"))
      (node (ref "U3") (pin "22") (pinfunction "GND_22") (pintype "bidirectional"))
      (node (ref "U3") (pin "25") (pinfunction "GND_25") (pintype "bidirectional"))
      (node (ref "U3") (pin "26") (pinfunction "GND_26") (pintype "bidirectional"))
      (node (ref "U3") (pin "27") (pinfunction "GND_27") (pintype "bidirectional"))
      (node (ref "U3") (pin "28") (pinfunction "GND_28") (pintype "bidirectional"))
      (node (ref "U3") (pin "29") (pinfunction "GND_29") (pintype "bidirectional"))
      (node (ref "U3") (pin "3") (pinfunction "GND_3") (pintype "bidirectional"))
      (node (ref "U3") (pin "30") (pinfunction "GND_30") (pintype "bidirectional"))
      (node (ref "U3") (pin "31") (pinfunction "GND_31") (pintype "bidirectional"))
      (node (ref "U3") (pin "32") (pinfunction "GND_32") (pintype "bidirectional"))
      (node (ref "U4") (pin "16") (pinfunction "GND_16") (pintype "bidirectional"))
      (node (ref "U4") (pin "22") (pinfunction "GND_22") (pintype "bidirectional"))
      (node (ref "U4") (pin "25") (pinfunction "GND_25") (pintype "bidirectional"))
      (node (ref "U4") (pin "26") (pinfunction "GND_26") (pintype "bidirectional"))
      (node (ref "U4") (pin "27") (pinfunction "GND_27") (pintype "bidirectional"))
      (node (ref "U4") (pin "28") (pinfunction "GND_28") (pintype "bidirectional"))
      (node (ref "U4") (pin "29") (pinfunction "GND_29") (pintype "bidirectional"))
      (node (ref "U4") (pin "3") (pinfunction "GND_3") (pintype "bidirectional"))
      (node (ref "U4") (pin "30") (pinfunction "GND_30") (pintype "bidirectional"))
      (node (ref "U4") (pin "31") (pinfunction "GND_31") (pintype "bidirectional"))
      (node (ref "U4") (pin "32") (pinfunction "GND_32") (pintype "bidirectional"))
      (node (ref "U5") (pin "10") (pinfunction "VSS_10") (pintype "bidirectional"))
    )
    (net (code "8") (name "I2C_SCL") (class "Default")
      (node (ref "JP1") (pin "6") (pinfunction "S_6") (pintype "passive"))
      (node (ref "U5") (pin "2") (pinfunction "SCL_2") (pintype "bidirectional"))
    )
    (net (code "9") (name "I2C_SDA") (class "Default")
      (node (ref "JP1") (pin "5") (pinfunction "S_5") (pintype "passive"))
      (node (ref "U5") (pin "3") (pinfunction "SDA_3") (pintype "bidirectional"))
    )
    (net (code "10") (name "Net-(C2-C1)") (class "Default")
      (node (ref "C2") (pin "1") (pinfunction "C1_1") (pintype "passive"))
      (node (ref "C3") (pin "1") (pinfunction "C1_1") (pintype "passive"))
      (node (ref "C33") (pin "1") (pinfunction "C1_1") (pintype "passive"))
      (node (ref "CON1") (pin "P$2") (pinfunction "S_P$2") (pintype "passive"))
      (node (ref "D1") (pin "C") (pinfunction "C_C") (pintype "passive"))
      (node (ref "L1") (pin "2") (pinfunction "2_2") (pintype "passive"))
      (node (ref "R32") (pin "2") (pinfunction "2_2") (pintype "passive"))
    )
    (net (code "11") (name "Net-(C6-C1)") (class "Default")
      (node (ref "C6") (pin "1") (pinfunction "C1_1") (pintype "passive"))
      (node (ref "U2") (pin "21") (pinfunction "TR/SS_21") (pintype "bidirectional"))
    )
    (net (code "12") (name "Net-(C7-C1)") (class "Default")
      (node (ref "C7") (pin "1") (pinfunction "C1_1") (pintype "passive"))
      (node (ref "U2") (pin "2") (pinfunction "INTVCC_2") (pintype "bidirectional"))
      (node (ref "U2") (pin "20") (pinfunction "SYNC/MODE_20") (pintype "bidirectional"))
    )
    (net (code "13") (name "Net-(C8-C2)") (class "Default")
      (node (ref "C8") (pin "2") (pinfunction "C2_2") (pintype "passive"))
      (node (ref "R3") (pin "1") (pinfunction "1_1") (pintype "passive"))
      (node (ref "R4") (pin "2") (pinfunction "2_2") (pintype "passive"))
      (node (ref "R6") (pin "1") (pinfunction "1_1") (pintype "passive"))
      (node (ref "U2") (pin "24") (pinfunction "FB_24") (pintype "bidirectional"))
    )
    (net (code "14") (name "Net-(C11-C1)") (class "Default")
      (node (ref "C11") (pin "1") (pinfunction "C1_1") (pintype "passive"))
      (node (ref "C12") (pin "1") (pinfunction "C1_1") (pintype "passive"))
      (node (ref "C8") (pin "1") (pinfunction "C1_1") (pintype "passive"))
      (node (ref "CON2") (pin "P$2") (pinfunction "S_P$2") (pintype "passive"))
      (node (ref "D4") (pin "C") (pinfunction "C_C") (pintype "passive"))
      (node (ref "L2") (pin "2") (pinfunction "2_2") (pintype "passive"))
      (node (ref "R3") (pin "2") (pinfunction "2_2") (pintype "passive"))
    )
    (net (code "15") (name "Net-(C13-C1)") (class "Default")
      (node (ref "C13") (pin "1") (pinfunction "C1_1") (pintype "passive"))
      (node (ref "C14") (pin "1") (pinfunction "C1_1") (pintype "passive"))
      (node (ref "C18") (pin "1") (pinfunction "C1_1") (pintype "passive"))
      (node (ref "C37") (pin "1") (pinfunction "C1_1") (pintype "passive"))
      (node (ref "D7") (pin "C") (pinfunction "C_C") (pintype "passive"))
      (node (ref "F2") (pin "1") (pinfunction "1_1") (pintype "passive"))
      (node (ref "U3") (pin "13") (pinfunction "VIN_13") (pintype "bidirectional"))
      (node (ref "U3") (pin "14") (pinfunction "VIN_14") (pintype "bidirectional"))
      (node (ref "U3") (pin "5") (pinfunction "VIN_5") (pintype "bidirectional"))
      (node (ref "U3") (pin "6") (pinfunction "VIN_6") (pintype "bidirectional"))
    )
    (net (code "16") (name "Net-(C15-C1)") (class "Default")
      (node (ref "C15") (pin "1") (pinfunction "C1_1") (pintype "passive"))
      (node (ref "U3") (pin "21") (pinfunction "TR/SS_21") (pintype "bidirectional"))
    )
    (net (code "17") (name "Net-(C16-C1)") (class "Default")
      (node (ref "C16") (pin "1") (pinfunction "C1_1") (pintype "passive"))
      (node (ref "U3") (pin "2") (pinfunction "INTVCC_2") (pintype "bidirectional"))
      (node (ref "U3") (pin "20") (pinfunction "SYNC/MODE_20") (pintype "bidirectional"))
    )
    (net (code "18") (name "Net-(C17-C1)") (class "Default")
      (node (ref "C17") (pin "1") (pinfunction "C1_1") (pintype "passive"))
      (node (ref "C20") (pin "1") (pinfunction "C1_1") (pintype "passive"))
      (node (ref "C21") (pin "1") (pinfunction "C1_1") (pintype "passive"))
      (node (ref "CON3") (pin "P$2") (pinfunction "S_P$2") (pintype "passive"))
      (node (ref "D5") (pin "C") (pinfunction "C_C") (pintype "passive"))
      (node (ref "L3") (pin "2") (pinfunction "2_2") (pintype "passive"))
      (node (ref "R8") (pin "2") (pinfunction "2_2") (pintype "passive"))
    )
    (net (code "19") (name "Net-(C17-C2)") (class "Default")
      (node (ref "C17") (pin "2") (pinfunction "C2_2") (pintype "passive"))
      (node (ref "R11") (pin "1") (pinfunction "1_1") (pintype "passive"))
      (node (ref "R8") (pin "1") (pinfunction "1_1") (pintype "passive"))
      (node (ref "R9") (pin "2") (pinfunction "2_2") (pintype "passive"))
      (node (ref "U3") (pin "24") (pinfunction "FB_24") (pintype "bidirectional"))
    )
    (net (code "20") (name "Net-(C22-C1)") (class "Default")
      (node (ref "C22") (pin "1") (pinfunction "C1_1") (pintype "passive"))
      (node (ref "C27") (pin "1") (pinfunction "C1_1") (pintype "passive"))
      (node (ref "C29") (pin "1") (pinfunction "C1_1") (pintype "passive"))
      (node (ref "C40") (pin "1") (pinfunction "C1_1") (pintype "passive"))
      (node (ref "D9") (pin "C") (pinfunction "C_C") (pintype "passive"))
      (node (ref "F4") (pin "1") (pinfunction "1_1") (pintype "passive"))
      (node (ref "U1") (pin "13") (pinfunction "VIN_13") (pintype "bidirectional"))
      (node (ref "U1") (pin "14") (pinfunction "VIN_14") (pintype "bidirectional"))
      (node (ref "U1") (pin "5") (pinfunction "VIN_5") (pintype "bidirectional"))
      (node (ref "U1") (pin "6") (pinfunction "VIN_6") (pintype "bidirectional"))
    )
    (net (code "21") (name "Net-(C23-C1)") (class "Default")
      (node (ref "C23") (pin "1") (pinfunction "C1_1") (pintype "passive"))
      (node (ref "C24") (pin "1") (pinfunction "C1_1") (pintype "passive"))
      (node (ref "C32") (pin "1") (pinfunction "C1_1") (pintype "passive"))
      (node (ref "C38") (pin "1") (pinfunction "C1_1") (pintype "passive"))
      (node (ref "D2") (pin "C") (pinfunction "C_C") (pintype "passive"))
      (node (ref "F1") (pin "1") (pinfunction "1_1") (pintype "passive"))
      (node (ref "U4") (pin "13") (pinfunction "VIN_13") (pintype "bidirectional"))
      (node (ref "U4") (pin "14") (pinfunction "VIN_14") (pintype "bidirectional"))
      (node (ref "U4") (pin "5") (pinfunction "VIN_5") (pintype "bidirectional"))
      (node (ref "U4") (pin "6") (pinfunction "VIN_6") (pintype "bidirectional"))
    )
    (net (code "22") (name "Net-(C25-C1)") (class "Default")
      (node (ref "C25") (pin "1") (pinfunction "C1_1") (pintype "passive"))
      (node (ref "U4") (pin "21") (pinfunction "TR/SS_21") (pintype "bidirectional"))
    )
    (net (code "23") (name "Net-(C26-C1)") (class "Default")
      (node (ref "C26") (pin "1") (pinfunction "C1_1") (pintype "passive"))
      (node (ref "U4") (pin "2") (pinfunction "INTVCC_2") (pintype "bidirectional"))
      (node (ref "U4") (pin "20") (pinfunction "SYNC/MODE_20") (pintype "bidirectional"))
    )
    (net (code "24") (name "Net-(C28-C1)") (class "Default")
      (node (ref "C28") (pin "1") (pinfunction "C1_1") (pintype "passive"))
      (node (ref "C35") (pin "1") (pinfunction "C1_1") (pintype "passive"))
      (node (ref "C36") (pin "1") (pinfunction "C1_1") (pintype "passive"))
      (node (ref "CON5") (pin "P$2") (pinfunction "S_P$2") (pintype "passive"))
      (node (ref "D6") (pin "C") (pinfunction "C_C") (pintype "passive"))
      (node (ref "L4") (pin "2") (pinfunction "2_2") (pintype "passive"))
      (node (ref "R13") (pin "2") (pinfunction "2_2") (pintype "passive"))
    )
    (net (code "25") (name "Net-(C28-C2)") (class "Default")
      (node (ref "C28") (pin "2") (pinfunction "C2_2") (pintype "passive"))
      (node (ref "R13") (pin "1") (pinfunction "1_1") (pintype "passive"))
      (node (ref "R14") (pin "2") (pinfunction "2_2") (pintype "passive"))
      (node (ref "R16") (pin "1") (pinfunction "1_1") (pintype "passive"))
      (node (ref "U4") (pin "24") (pinfunction "FB_24") (pintype "bidirectional"))
    )
    (net (code "26") (name "Net-(C30-C1)") (class "Default")
      (node (ref "C30") (pin "1") (pinfunction "C1_1") (pintype "passive"))
      (node (ref "U1") (pin "2") (pinfunction "INTVCC_2") (pintype "bidirectional"))
      (node (ref "U1") (pin "20") (pinfunction "SYNC/MODE_20") (pintype "bidirectional"))
    )
    (net (code "27") (name "Net-(C31-C1)") (class "Default")
      (node (ref "C31") (pin "1") (pinfunction "C1_1") (pintype "passive"))
      (node (ref "U1") (pin "21") (pinfunction "TR/SS_21") (pintype "bidirectional"))
    )
    (net (code "28") (name "Net-(C33-C2)") (class "Default")
      (node (ref "C33") (pin "2") (pinfunction "C2_2") (pintype "passive"))
      (node (ref "R24") (pin "1") (pinfunction "1_1") (pintype "passive"))
      (node (ref "R32") (pin "1") (pinfunction "1_1") (pintype "passive"))
      (node (ref "R33") (pin "2") (pinfunction "2_2") (pintype "passive"))
      (node (ref "U1") (pin "24") (pinfunction "FB_24") (pintype "bidirectional"))
    )
    (net (code "29") (name "Net-(C39-C1)") (class "Default")
      (node (ref "C39") (pin "1") (pinfunction "C1_1") (pintype "passive"))
      (node (ref "C4") (pin "1") (pinfunction "C1_1") (pintype "passive"))
      (node (ref "C5") (pin "1") (pinfunction "C1_1") (pintype "passive"))
      (node (ref "C9") (pin "1") (pinfunction "C1_1") (pintype "passive"))
      (node (ref "D8") (pin "C") (pinfunction "C_C") (pintype "passive"))
      (node (ref "F3") (pin "1") (pinfunction "1_1") (pintype "passive"))
      (node (ref "U2") (pin "13") (pinfunction "VIN_13") (pintype "bidirectional"))
      (node (ref "U2") (pin "14") (pinfunction "VIN_14") (pintype "bidirectional"))
      (node (ref "U2") (pin "5") (pinfunction "VIN_5") (pintype "bidirectional"))
      (node (ref "U2") (pin "6") (pinfunction "VIN_6") (pintype "bidirectional"))
    )
    (net (code "30") (name "Net-(D3-PadA)") (class "Default")
      (node (ref "D3") (pin "A") (pinfunction "A_A") (pintype "passive"))
      (node (ref "R34") (pin "1") (pinfunction "1_1") (pintype "passive"))
    )
    (net (code "31") (name "Net-(L1-Pad1)") (class "Default")
      (node (ref "L1") (pin "1") (pinfunction "1_1") (pintype "passive"))
      (node (ref "U1") (pin "10") (pinfunction "SW_10") (pintype "bidirectional"))
      (node (ref "U1") (pin "11") (pinfunction "SW_11") (pintype "bidirectional"))
      (node (ref "U1") (pin "12") (pinfunction "SW_12") (pintype "bidirectional"))
      (node (ref "U1") (pin "8") (pinfunction "SW_8") (pintype "bidirectional"))
      (node (ref "U1") (pin "9") (pinfunction "SW_9") (pintype "bidirectional"))
    )
    (net (code "32") (name "Net-(L2-Pad1)") (class "Default")
      (node (ref "L2") (pin "1") (pinfunction "1_1") (pintype "passive"))
      (node (ref "U2") (pin "10") (pinfunction "SW_10") (pintype "bidirectional"))
      (node (ref "U2") (pin "11") (pinfunction "SW_11") (pintype "bidirectional"))
      (node (ref "U2") (pin "12") (pinfunction "SW_12") (pintype "bidirectional"))
      (node (ref "U2") (pin "8") (pinfunction "SW_8") (pintype "bidirectional"))
      (node (ref "U2") (pin "9") (pinfunction "SW_9") (pintype "bidirectional"))
    )
    (net (code "33") (name "Net-(L3-Pad1)") (class "Default")
      (node (ref "L3") (pin "1") (pinfunction "1_1") (pintype "passive"))
      (node (ref "U3") (pin "10") (pinfunction "SW_10") (pintype "bidirectional"))
      (node (ref "U3") (pin "11") (pinfunction "SW_11") (pintype "bidirectional"))
      (node (ref "U3") (pin "12") (pinfunction "SW_12") (pintype "bidirectional"))
      (node (ref "U3") (pin "8") (pinfunction "SW_8") (pintype "bidirectional"))
      (node (ref "U3") (pin "9") (pinfunction "SW_9") (pintype "bidirectional"))
    )
    (net (code "34") (name "Net-(L4-Pad1)") (class "Default")
      (node (ref "L4") (pin "1") (pinfunction "1_1") (pintype "passive"))
      (node (ref "U4") (pin "10") (pinfunction "SW_10") (pintype "bidirectional"))
      (node (ref "U4") (pin "11") (pinfunction "SW_11") (pintype "bidirectional"))
      (node (ref "U4") (pin "12") (pinfunction "SW_12") (pintype "bidirectional"))
      (node (ref "U4") (pin "8") (pinfunction "SW_8") (pintype "bidirectional"))
      (node (ref "U4") (pin "9") (pinfunction "SW_9") (pintype "bidirectional"))
    )
    (net (code "35") (name "Net-(U1-RT)") (class "Default")
      (node (ref "R29") (pin "2") (pinfunction "2_2") (pintype "passive"))
      (node (ref "U1") (pin "18") (pinfunction "RT_18") (pintype "bidirectional"))
    )
    (net (code "36") (name "Net-(U2-RT)") (class "Default")
      (node (ref "R2") (pin "2") (pinfunction "2_2") (pintype "passive"))
      (node (ref "U2") (pin "18") (pinfunction "RT_18") (pintype "bidirectional"))
    )
    (net (code "37") (name "Net-(U3-RT)") (class "Default")
      (node (ref "R7") (pin "2") (pinfunction "2_2") (pintype "passive"))
      (node (ref "U3") (pin "18") (pinfunction "RT_18") (pintype "bidirectional"))
    )
    (net (code "38") (name "Net-(U4-RT)") (class "Default")
      (node (ref "R12") (pin "2") (pinfunction "2_2") (pintype "passive"))
      (node (ref "U4") (pin "18") (pinfunction "RT_18") (pintype "bidirectional"))
    )
    (net (code "39") (name "TEC1_VADJ") (class "Default")
      (node (ref "R24") (pin "2") (pinfunction "2_2") (pintype "passive"))
      (node (ref "U5") (pin "6") (pinfunction "VOUTA_6") (pintype "bidirectional"))
    )
    (net (code "40") (name "TEC2_VADJ") (class "Default")
      (node (ref "R6") (pin "2") (pinfunction "2_2") (pintype "passive"))
      (node (ref "U5") (pin "7") (pinfunction "VOUTB_7") (pintype "bidirectional"))
    )
    (net (code "41") (name "TEC3_VADJ") (class "Default")
      (node (ref "R11") (pin "2") (pinfunction "2_2") (pintype "passive"))
      (node (ref "U5") (pin "8") (pinfunction "VOUTC_8") (pintype "bidirectional"))
    )
    (net (code "42") (name "TEC4_VADJ") (class "Default")
      (node (ref "R16") (pin "2") (pinfunction "2_2") (pintype "passive"))
      (node (ref "U5") (pin "9") (pinfunction "VOUTD_9") (pintype "bidirectional"))
    )
    (net (code "43") (name "VIN") (class "Default")
      (node (ref "CON4") (pin "P$2") (pinfunction "S_P$2") (pintype "passive"))
      (node (ref "F1") (pin "2") (pinfunction "2_2") (pintype "passive"))
      (node (ref "F2") (pin "2") (pinfunction "2_2") (pintype "passive"))
      (node (ref "F3") (pin "2") (pinfunction "2_2") (pintype "passive"))
      (node (ref "F4") (pin "2") (pinfunction "2_2") (pintype "passive"))
    )
    (net (code "44") (name "unconnected-(U1-BST-Pad7)") (class "Default")
      (node (ref "U1") (pin "7") (pinfunction "BST_7") (pintype "bidirectional"))
    )
    (net (code "45") (name "unconnected-(U1-CLKOUT-Pad19)") (class "Default")
      (node (ref "U1") (pin "19") (pinfunction "CLKOUT_19") (pintype "bidirectional"))
    )
    (net (code "46") (name "unconnected-(U1-PG-Pad23)") (class "Default")
      (node (ref "U1") (pin "23") (pinfunction "PG_23") (pintype "bidirectional"))
    )
    (net (code "47") (name "unconnected-(U2-BST-Pad7)") (class "Default")
      (node (ref "U2") (pin "7") (pinfunction "BST_7") (pintype "bidirectional"))
    )
    (net (code "48") (name "unconnected-(U2-CLKOUT-Pad19)") (class "Default")
      (node (ref "U2") (pin "19") (pinfunction "CLKOUT_19") (pintype "bidirectional"))
    )
    (net (code "49") (name "unconnected-(U2-PG-Pad23)") (class "Default")
      (node (ref "U2") (pin "23") (pinfunction "PG_23") (pintype "bidirectional"))
    )
    (net (code "50") (name "unconnected-(U3-BST-Pad7)") (class "Default")
      (node (ref "U3") (pin "7") (pinfunction "BST_7") (pintype "bidirectional"))
    )
    (net (code "51") (name "unconnected-(U3-CLKOUT-Pad19)") (class "Default")
      (node (ref "U3") (pin "19") (pinfunction "CLKOUT_19") (pintype "bidirectional"))
    )
    (net (code "52") (name "unconnected-(U3-PG-Pad23)") (class "Default")
      (node (ref "U3") (pin "23") (pinfunction "PG_23") (pintype "bidirectional"))
    )
    (net (code "53") (name "unconnected-(U4-BST-Pad7)") (class "Default")
      (node (ref "U4") (pin "7") (pinfunction "BST_7") (pintype "bidirectional"))
    )
    (net (code "54") (name "unconnected-(U4-CLKOUT-Pad19)") (class "Default")
      (node (ref "U4") (pin "19") (pinfunction "CLKOUT_19") (pintype "bidirectional"))
    )
    (net (code "55") (name "unconnected-(U4-PG-Pad23)") (class "Default")
      (node (ref "U4") (pin "23") (pinfunction "PG_23") (pintype "bidirectional"))
    )
    (net (code "56") (name "unconnected-(U5-~{BSY}-Pad5)") (class "Default")
      (node (ref "U5") (pin "5") (pinfunction "~{BSY}_5") (pintype "bidirectional"))
    )
  )
)
